# UIO_INT.net
KiCad netlist of a schematic drawn in Altium Designer
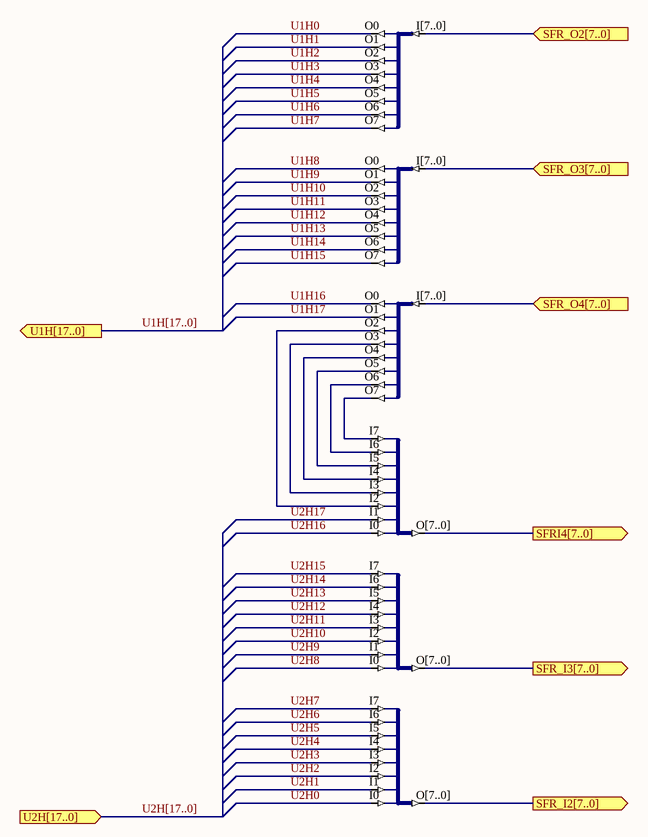
[diagram p0: UIO_INT.SchDoc]

(export (version "E")
  (design (tool "Eeschema 10.0.6"))
  (components
    (comp (ref "U198")
      (value "J8B_8S")
      (description "8-Bit input bus to 8 single pin outputs")
      (fields (field (name "PUBLISHER") "Altium Limited"))
      (libsource (lib "FPGA Generic") (part "J8B_8S"))
    )
    (comp (ref "U199")
      (value "J8B_8S")
      (description "8-Bit input bus to 8 single pin outputs")
      (fields (field (name "PUBLISHER") "Altium Limited"))
      (libsource (lib "FPGA Generic") (part "J8B_8S"))
    )
    (comp (ref "U200")
      (value "J8B_8S")
      (description "8-Bit input bus to 8 single pin outputs")
      (fields (field (name "PUBLISHER") "Altium Limited"))
      (libsource (lib "FPGA Generic") (part "J8B_8S"))
    )
    (comp (ref "U201")
      (value "J8S_8B")
      (description "8 Single pin inputs to single 8-Bit output bus")
      (fields (field (name "PUBLISHER") "Altium Limited"))
      (libsource (lib "FPGA Generic") (part "J8S_8B"))
    )
    (comp (ref "U202")
      (value "J8S_8B")
      (description "8 Single pin inputs to single 8-Bit output bus")
      (fields (field (name "PUBLISHER") "Altium Limited"))
      (libsource (lib "FPGA Generic") (part "J8S_8B"))
    )
    (comp (ref "U203")
      (value "J8S_8B")
      (description "8 Single pin inputs to single 8-Bit output bus")
      (fields (field (name "PUBLISHER") "Altium Limited"))
      (libsource (lib "FPGA Generic") (part "J8S_8B"))
    )
  )
  (nets
    (net (code "49") (name "/SFRI4[7..0]") (class "Default")
      (node (ref "U201") (pin "O[7..0]") (pinfunction "O[7..0]_O[7..0]") (pintype "output"))
    )
    (net (code "50") (name "/SFR_I2[7..0]") (class "Default")
      (node (ref "U203") (pin "O[7..0]") (pinfunction "O[7..0]_O[7..0]") (pintype "output"))
    )
    (net (code "51") (name "/SFR_I3[7..0]") (class "Default")
      (node (ref "U202") (pin "O[7..0]") (pinfunction "O[7..0]_O[7..0]") (pintype "output"))
    )
    (net (code "52") (name "/SFR_O2[7..0]") (class "Default")
      (node (ref "U198") (pin "I[7..0]") (pinfunction "I[7..0]_I[7..0]") (pintype "input"))
    )
    (net (code "53") (name "/SFR_O3[7..0]") (class "Default")
      (node (ref "U199") (pin "I[7..0]") (pinfunction "I[7..0]_I[7..0]") (pintype "input"))
    )
    (net (code "54") (name "/SFR_O4[7..0]") (class "Default")
      (node (ref "U200") (pin "I[7..0]") (pinfunction "I[7..0]_I[7..0]") (pintype "input"))
    )
    (net (code "55") (name "/U1H0") (class "Default")
      (node (ref "U198") (pin "O0") (pinfunction "O0_O0") (pintype "output"))
    )
    (net (code "56") (name "/U1H1") (class "Default")
      (node (ref "U198") (pin "O1") (pinfunction "O1_O1") (pintype "output"))
    )
    (net (code "57") (name "/U1H2") (class "Default")
      (node (ref "U198") (pin "O2") (pinfunction "O2_O2") (pintype "output"))
    )
    (net (code "58") (name "/U1H3") (class "Default")
      (node (ref "U198") (pin "O3") (pinfunction "O3_O3") (pintype "output"))
    )
    (net (code "59") (name "/U1H4") (class "Default")
      (node (ref "U198") (pin "O4") (pinfunction "O4_O4") (pintype "output"))
    )
    (net (code "60") (name "/U1H5") (class "Default")
      (node (ref "U198") (pin "O5") (pinfunction "O5_O5") (pintype "output"))
    )
    (net (code "61") (name "/U1H6") (class "Default")
      (node (ref "U198") (pin "O6") (pinfunction "O6_O6") (pintype "output"))
    )
    (net (code "62") (name "/U1H7") (class "Default")
      (node (ref "U198") (pin "O7") (pinfunction "O7_O7") (pintype "output"))
    )
    (net (code "63") (name "/U1H8") (class "Default")
      (node (ref "U199") (pin "O0") (pinfunction "O0_O0") (pintype "output"))
    )
    (net (code "64") (name "/U1H9") (class "Default")
      (node (ref "U199") (pin "O1") (pinfunction "O1_O1") (pintype "output"))
    )
    (net (code "65") (name "/U1H10") (class "Default")
      (node (ref "U199") (pin "O2") (pinfunction "O2_O2") (pintype "output"))
    )
    (net (code "66") (name "/U1H11") (class "Default")
      (node (ref "U199") (pin "O3") (pinfunction "O3_O3") (pintype "output"))
    )
    (net (code "67") (name "/U1H12") (class "Default")
      (node (ref "U199") (pin "O4") (pinfunction "O4_O4") (pintype "output"))
    )
    (net (code "68") (name "/U1H13") (class "Default")
      (node (ref "U199") (pin "O5") (pinfunction "O5_O5") (pintype "output"))
    )
    (net (code "69") (name "/U1H14") (class "Default")
      (node (ref "U199") (pin "O6") (pinfunction "O6_O6") (pintype "output"))
    )
    (net (code "70") (name "/U1H15") (class "Default")
      (node (ref "U199") (pin "O7") (pinfunction "O7_O7") (pintype "output"))
    )
    (net (code "71") (name "/U1H16") (class "Default")
      (node (ref "U200") (pin "O0") (pinfunction "O0_O0") (pintype "output"))
    )
    (net (code "72") (name "/U1H17") (class "Default")
      (node (ref "U200") (pin "O1") (pinfunction "O1_O1") (pintype "output"))
    )
    (net (code "74") (name "/U2H0") (class "Default")
      (node (ref "U203") (pin "I0") (pinfunction "I0_I0") (pintype "input"))
    )
    (net (code "75") (name "/U2H1") (class "Default")
      (node (ref "U203") (pin "I1") (pinfunction "I1_I1") (pintype "input"))
    )
    (net (code "76") (name "/U2H2") (class "Default")
      (node (ref "U203") (pin "I2") (pinfunction "I2_I2") (pintype "input"))
    )
    (net (code "77") (name "/U2H3") (class "Default")
      (node (ref "U203") (pin "I3") (pinfunction "I3_I3") (pintype "input"))
    )
    (net (code "78") (name "/U2H4") (class "Default")
      (node (ref "U203") (pin "I4") (pinfunction "I4_I4") (pintype "input"))
    )
    (net (code "79") (name "/U2H5") (class "Default")
      (node (ref "U203") (pin "I5") (pinfunction "I5_I5") (pintype "input"))
    )
    (net (code "80") (name "/U2H6") (class "Default")
      (node (ref "U203") (pin "I6") (pinfunction "I6_I6") (pintype "input"))
    )
    (net (code "81") (name "/U2H7") (class "Default")
      (node (ref "U203") (pin "I7") (pinfunction "I7_I7") (pintype "input"))
    )
    (net (code "82") (name "/U2H8") (class "Default")
      (node (ref "U202") (pin "I0") (pinfunction "I0_I0") (pintype "input"))
    )
    (net (code "83") (name "/U2H9") (class "Default")
      (node (ref "U202") (pin "I1") (pinfunction "I1_I1") (pintype "input"))
    )
    (net (code "84") (name "/U2H10") (class "Default")
      (node (ref "U202") (pin "I2") (pinfunction "I2_I2") (pintype "input"))
    )
    (net (code "85") (name "/U2H11") (class "Default")
      (node (ref "U202") (pin "I3") (pinfunction "I3_I3") (pintype "input"))
    )
    (net (code "86") (name "/U2H12") (class "Default")
      (node (ref "U202") (pin "I4") (pinfunction "I4_I4") (pintype "input"))
    )
    (net (code "87") (name "/U2H13") (class "Default")
      (node (ref "U202") (pin "I5") (pinfunction "I5_I5") (pintype "input"))
    )
    (net (code "88") (name "/U2H14") (class "Default")
      (node (ref "U202") (pin "I6") (pinfunction "I6_I6") (pintype "input"))
    )
    (net (code "89") (name "/U2H15") (class "Default")
      (node (ref "U202") (pin "I7") (pinfunction "I7_I7") (pintype "input"))
    )
    (net (code "90") (name "/U2H16") (class "Default")
      (node (ref "U201") (pin "I0") (pinfunction "I0_I0") (pintype "input"))
    )
    (net (code "91") (name "/U2H17") (class "Default")
      (node (ref "U201") (pin "I1") (pinfunction "I1_I1") (pintype "input"))
    )
    (net (code "93") (name "Net-(U200-PadO2)") (class "Default")
      (node (ref "U200") (pin "O2") (pinfunction "O2_O2") (pintype "output"))
      (node (ref "U201") (pin "I2") (pinfunction "I2_I2") (pintype "input"))
    )
    (net (code "94") (name "Net-(U200-PadO3)") (class "Default")
      (node (ref "U200") (pin "O3") (pinfunction "O3_O3") (pintype "output"))
      (node (ref "U201") (pin "I3") (pinfunction "I3_I3") (pintype "input"))
    )
    (net (code "95") (name "Net-(U200-PadO4)") (class "Default")
      (node (ref "U200") (pin "O4") (pinfunction "O4_O4") (pintype "output"))
      (node (ref "U201") (pin "I4") (pinfunction "I4_I4") (pintype "input"))
    )
    (net (code "96") (name "Net-(U200-PadO5)") (class "Default")
      (node (ref "U200") (pin "O5") (pinfunction "O5_O5") (pintype "output"))
      (node (ref "U201") (pin "I5") (pinfunction "I5_I5") (pintype "input"))
    )
    (net (code "97") (name "Net-(U200-PadO6)") (class "Default")
      (node (ref "U200") (pin "O6") (pinfunction "O6_O6") (pintype "output"))
      (node (ref "U201") (pin "I6") (pinfunction "I6_I6") (pintype "input"))
    )
    (net (code "98") (name "Net-(U200-PadO7)") (class "Default")
      (node (ref "U200") (pin "O7") (pinfunction "O7_O7") (pintype "output"))
      (node (ref "U201") (pin "I7") (pinfunction "I7_I7") (pintype "input"))
    )
  )
)
